# CPM-_Circuital_Printing_Machine_2020-06-.net
KiCad netlist of a schematic drawn in EasyEDA
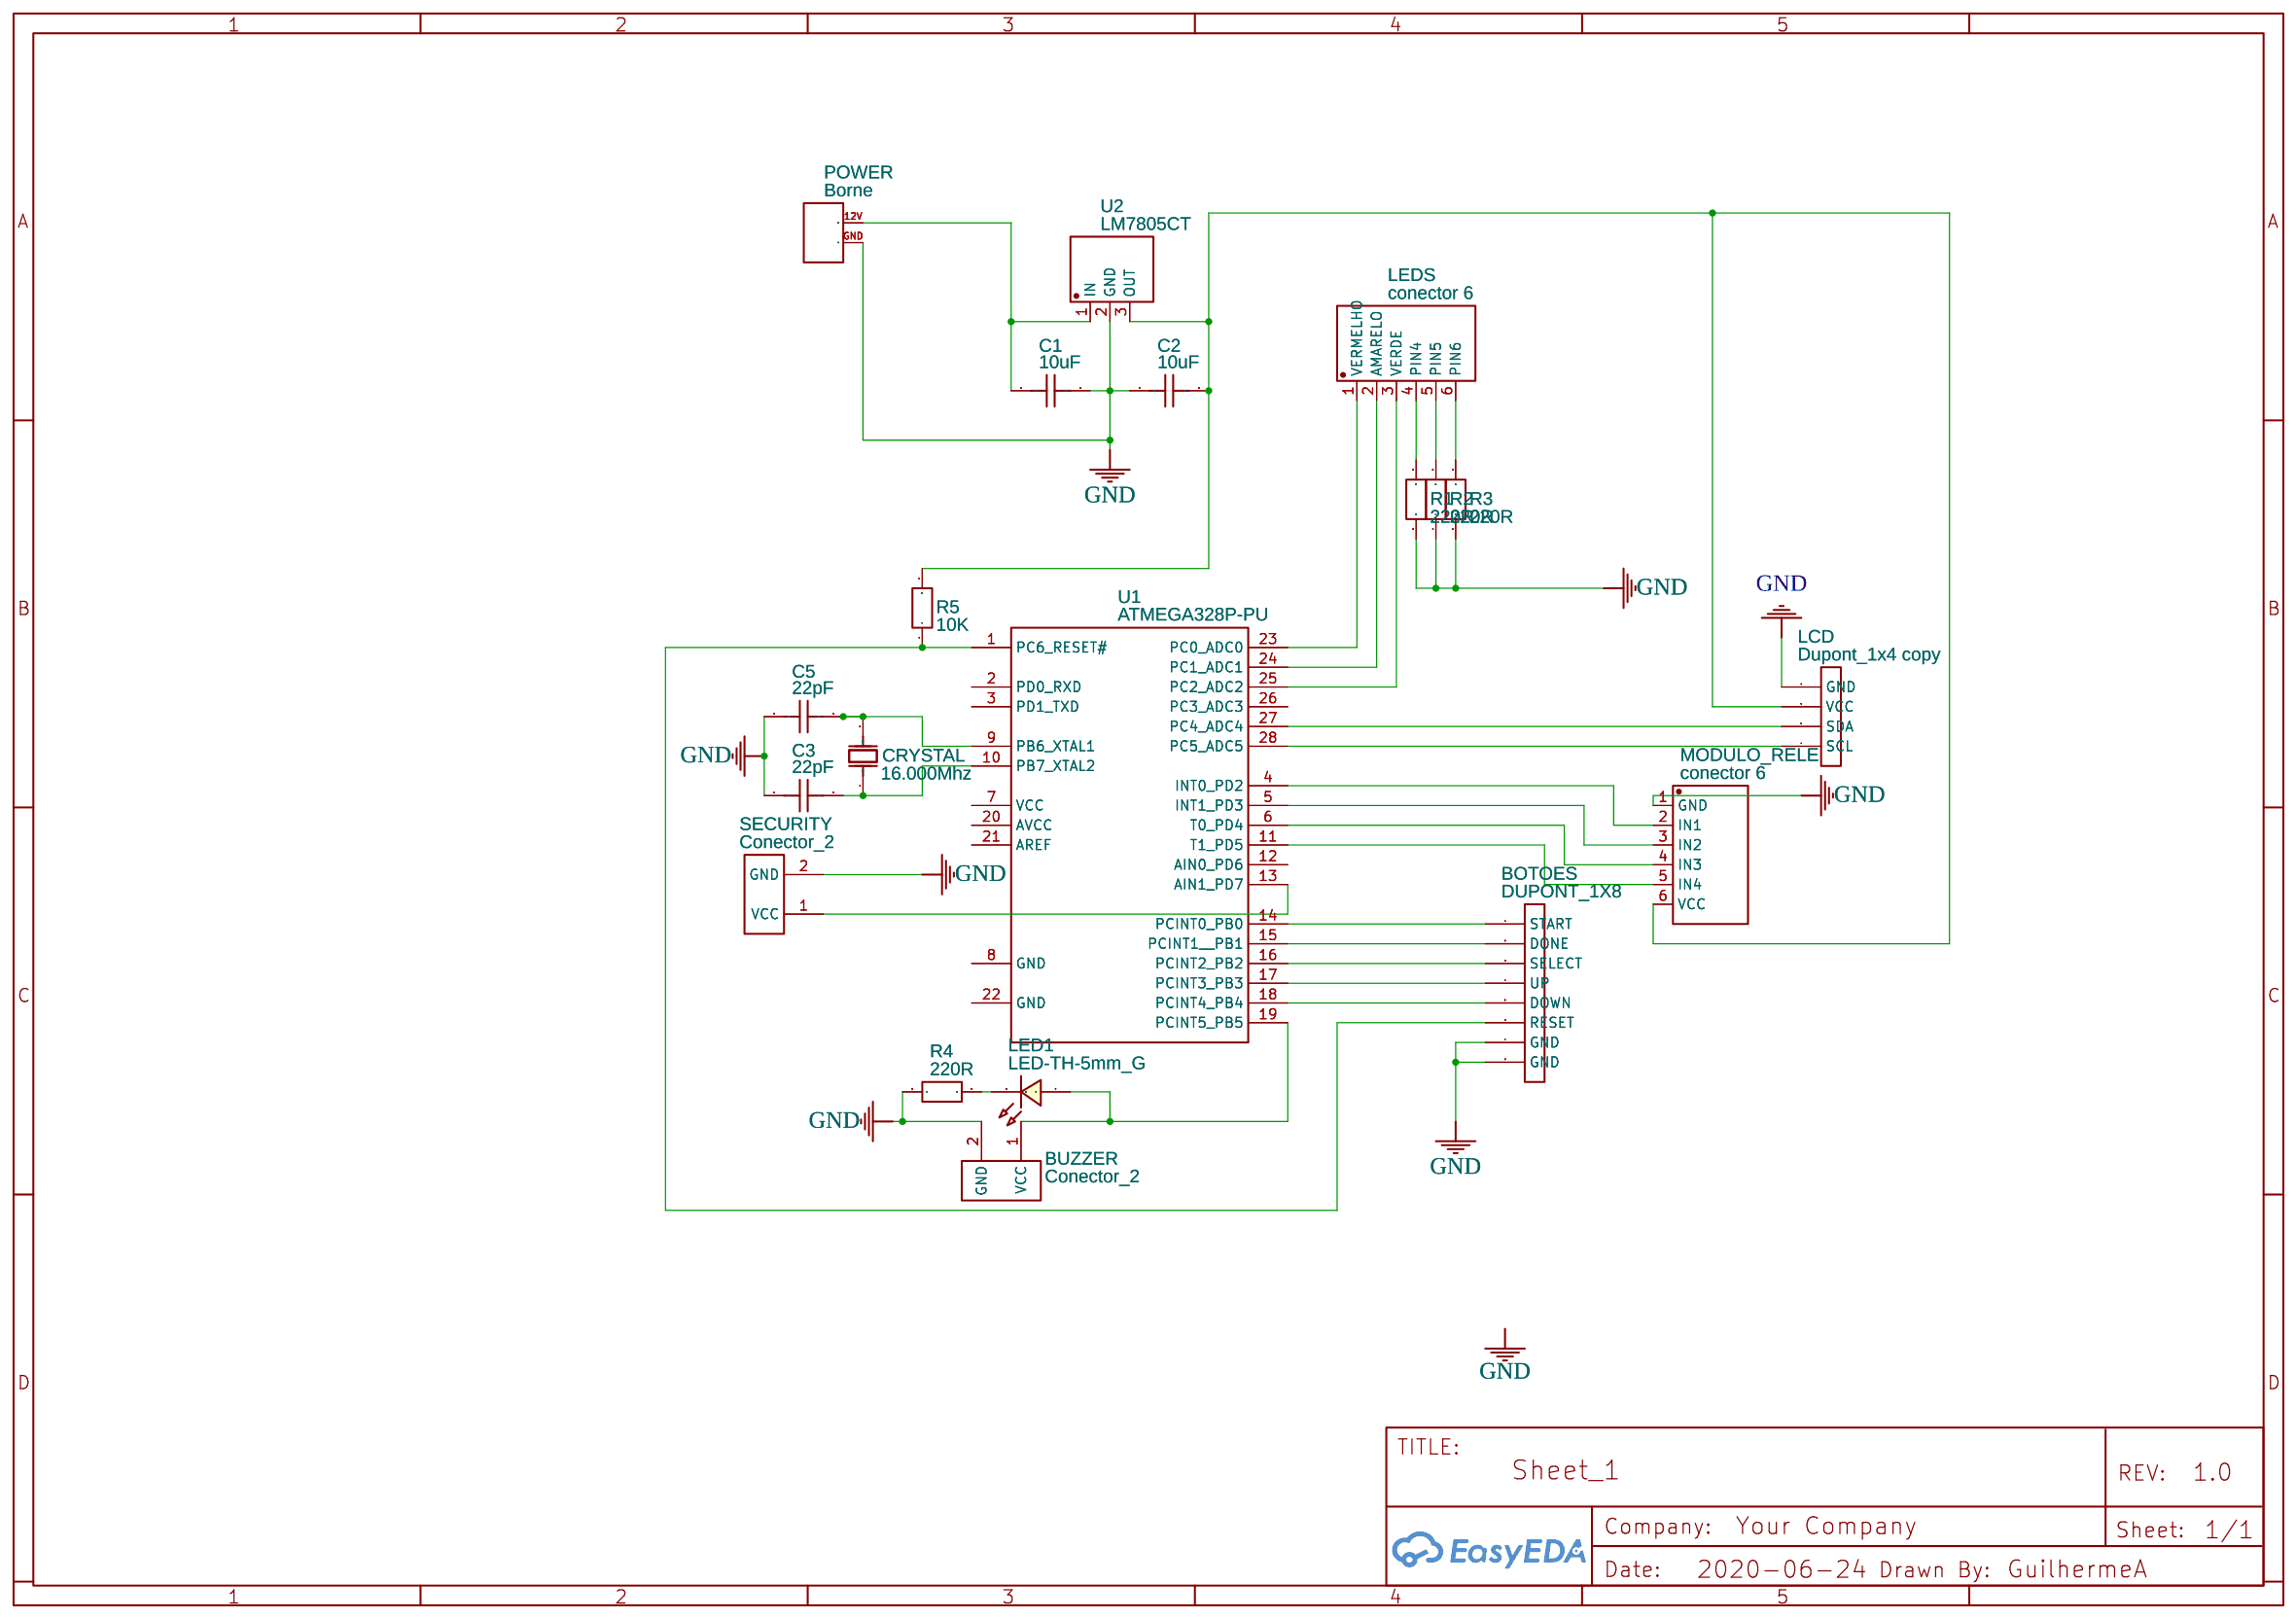
[diagram p0: schematic sheet]

(export (version "E")
  (design (tool "Eeschema 10.0.6"))
  (components
    (comp (ref "BOTOES")
      (value "DUPONT_1X8")
      (fields (field (name "BOM_Manufacturer Part") "Conector_dupont"))
      (libsource (lib "") (part "DUPONT_1X8"))
    )
    (comp (ref "BUZZER")
      (value "Conector_2")
      (fields (field (name "BOM_Manufacturer Part") "Conector2"))
      (libsource (lib "") (part "Conector_2"))
    )
    (comp (ref "C1") (value "10uF") (libsource (lib "") (part "C_RAD-0.1_US")))
    (comp (ref "C2") (value "10uF") (libsource (lib "") (part "C_RAD-0.1_US")))
    (comp (ref "C3") (value "22pF") (libsource (lib "") (part "C_RAD-0.1_US")))
    (comp (ref "C5") (value "22pF") (libsource (lib "") (part "C_RAD-0.1_US")))
    (comp (ref "CRYSTAL")
      (value "16.000Mhz")
      (fields
        (field (name "BOM_Manufacturer Part") "5S0-2700A2020-00")
        (field (name "BOM_Supplier Part") "C389767")
      )
      (libsource (lib "") (part "5S0-2700A2020-00"))
    )
    (comp (ref "LCD")
      (value "Dupont_1x4 copy")
      (fields (field (name "BOM_Manufacturer Part") "Conector_dupont"))
      (libsource (lib "") (part "Dupont_1x4 copy"))
    )
    (comp (ref "LED1")
      (value "LED-TH-5mm_G")
      (fields
        (field (name "BOM_Manufacturer Part") "333-2SYGD/S530-E2")
        (field (name "BOM_Supplier Part") "C88163")
      )
      (libsource (lib "") (part "LED-TH-5mm_G"))
    )
    (comp (ref "LEDS")
      (value "conector 6")
      (fields
        (field (name "BOM_Manufacturer Part") "425Connectors- -07P-2.5mmWhite Grey")
        (field (name "BOM_Supplier Part") "C89538")
      )
      (libsource (lib "") (part "conector 6"))
    )
    (comp (ref "MODULO_RELE")
      (value "conector 6")
      (fields
        (field (name "BOM_Manufacturer Part") "425Connectors- -07P-2.5mmWhite Grey")
        (field (name "BOM_Supplier Part") "C89538")
      )
      (libsource (lib "") (part "conector 6_1"))
    )
    (comp (ref "POWER") (value "Borne") (libsource (lib "") (part "Borne")))
    (comp (ref "R1") (value "220R") (libsource (lib "") (part "R_AXIAL-0.3_EU")))
    (comp (ref "R2") (value "220R") (libsource (lib "") (part "R_AXIAL-0.3_EU")))
    (comp (ref "R3") (value "220R") (libsource (lib "") (part "R_AXIAL-0.3_EU")))
    (comp (ref "R4") (value "220R") (libsource (lib "") (part "R_AXIAL-0.3_EU_1")))
    (comp (ref "R5") (value "10K") (libsource (lib "") (part "R_AXIAL-0.3_EU")))
    (comp (ref "SECURITY")
      (value "Conector_2")
      (fields (field (name "BOM_Manufacturer Part") "Conector2"))
      (libsource (lib "") (part "Conector_2_1"))
    )
    (comp (ref "U1")
      (value "ATMEGA328P-PU")
      (fields (field (name "BOM_Supplier Part") "C33901"))
      (libsource (lib "") (part "ATMEGA328P-PU"))
    )
    (comp (ref "U2")
      (value "LM7805CT")
      (fields (field (name "BOM_Supplier Part") "C22146"))
      (libsource (lib "") (part "LM7805CT"))
    )
  )
  (nets
    (net (code "1") (name "GND") (class "Default")
      (node (ref "BOTOES") (pin "7") (pinfunction "GND_7") (pintype "unspecified"))
      (node (ref "BOTOES") (pin "8") (pinfunction "GND_8") (pintype "unspecified"))
      (node (ref "BUZZER") (pin "2") (pinfunction "GND_2") (pintype "unspecified"))
      (node (ref "C1") (pin "2") (pinfunction "2_2") (pintype "unspecified"))
      (node (ref "C2") (pin "1") (pinfunction "1_1") (pintype "unspecified"))
      (node (ref "C3") (pin "1") (pinfunction "1_1") (pintype "unspecified"))
      (node (ref "C5") (pin "1") (pinfunction "1_1") (pintype "unspecified"))
      (node (ref "LCD") (pin "1") (pinfunction "GND_1") (pintype "unspecified"))
      (node (ref "MODULO_RELE") (pin "1") (pinfunction "GND_1") (pintype "unspecified"))
      (node (ref "POWER") (pin "GND") (pinfunction "1_GND") (pintype "unspecified"))
      (node (ref "R1") (pin "1") (pinfunction "1_1") (pintype "unspecified"))
      (node (ref "R2") (pin "1") (pinfunction "1_1") (pintype "unspecified"))
      (node (ref "R3") (pin "1") (pinfunction "1_1") (pintype "unspecified"))
      (node (ref "R4") (pin "2") (pinfunction "2_2") (pintype "unspecified"))
      (node (ref "SECURITY") (pin "2") (pinfunction "GND_2") (pintype "unspecified"))
      (node (ref "U2") (pin "2") (pinfunction "GND_2") (pintype "unspecified"))
    )
    (net (code "2") (name "Net-(BOTOES-DONE)") (class "Default")
      (node (ref "BOTOES") (pin "2") (pinfunction "DONE_2") (pintype "unspecified"))
      (node (ref "U1") (pin "15") (pinfunction "PCINT1__PB1_15") (pintype "bidirectional"))
    )
    (net (code "3") (name "Net-(BOTOES-DOWN)") (class "Default")
      (node (ref "BOTOES") (pin "5") (pinfunction "DOWN_5") (pintype "unspecified"))
      (node (ref "U1") (pin "18") (pinfunction "PCINT4_PB4_18") (pintype "bidirectional"))
    )
    (net (code "4") (name "Net-(BOTOES-RESET)") (class "Default")
      (node (ref "BOTOES") (pin "6") (pinfunction "RESET_6") (pintype "unspecified"))
      (node (ref "R5") (pin "1") (pinfunction "1_1") (pintype "unspecified"))
      (node (ref "U1") (pin "1") (pinfunction "PC6_RESET#_1") (pintype "bidirectional"))
    )
    (net (code "5") (name "Net-(BOTOES-SELECT)") (class "Default")
      (node (ref "BOTOES") (pin "3") (pinfunction "SELECT_3") (pintype "unspecified"))
      (node (ref "U1") (pin "16") (pinfunction "PCINT2_PB2_16") (pintype "bidirectional"))
    )
    (net (code "6") (name "Net-(BOTOES-START)") (class "Default")
      (node (ref "BOTOES") (pin "1") (pinfunction "START_1") (pintype "unspecified"))
      (node (ref "U1") (pin "14") (pinfunction "PCINT0_PB0_14") (pintype "bidirectional"))
    )
    (net (code "7") (name "Net-(BOTOES-UP)") (class "Default")
      (node (ref "BOTOES") (pin "4") (pinfunction "UP_4") (pintype "unspecified"))
      (node (ref "U1") (pin "17") (pinfunction "PCINT3_PB3_17") (pintype "bidirectional"))
    )
    (net (code "8") (name "Net-(BUZZER-VCC)") (class "Default")
      (node (ref "BUZZER") (pin "1") (pinfunction "VCC_1") (pintype "unspecified"))
      (node (ref "LED1") (pin "1") (pinfunction "1_1") (pintype "unspecified"))
      (node (ref "U1") (pin "19") (pinfunction "PCINT5_PB5_19") (pintype "bidirectional"))
    )
    (net (code "9") (name "Net-(CRYSTAL-OSC1)") (class "Default")
      (node (ref "C3") (pin "2") (pinfunction "2_2") (pintype "unspecified"))
      (node (ref "CRYSTAL") (pin "1") (pinfunction "OSC1_1") (pintype "input"))
      (node (ref "U1") (pin "10") (pinfunction "PB7_XTAL2_10") (pintype "bidirectional"))
    )
    (net (code "10") (name "Net-(CRYSTAL-OSC2)") (class "Default")
      (node (ref "C5") (pin "2") (pinfunction "2_2") (pintype "unspecified"))
      (node (ref "CRYSTAL") (pin "2") (pinfunction "OSC2_2") (pintype "input"))
      (node (ref "U1") (pin "9") (pinfunction "PB6_XTAL1_9") (pintype "bidirectional"))
    )
    (net (code "11") (name "Net-(LCD-SCL)") (class "Default")
      (node (ref "LCD") (pin "4") (pinfunction "SCL_4") (pintype "unspecified"))
      (node (ref "U1") (pin "28") (pinfunction "PC5_ADC5_28") (pintype "bidirectional"))
    )
    (net (code "12") (name "Net-(LCD-SDA)") (class "Default")
      (node (ref "LCD") (pin "3") (pinfunction "SDA_3") (pintype "unspecified"))
      (node (ref "U1") (pin "27") (pinfunction "PC4_ADC4_27") (pintype "bidirectional"))
    )
    (net (code "13") (name "Net-(LCD-VCC)") (class "Default")
      (node (ref "C2") (pin "2") (pinfunction "2_2") (pintype "unspecified"))
      (node (ref "LCD") (pin "2") (pinfunction "VCC_2") (pintype "unspecified"))
      (node (ref "MODULO_RELE") (pin "6") (pinfunction "VCC_6") (pintype "unspecified"))
      (node (ref "R5") (pin "2") (pinfunction "2_2") (pintype "unspecified"))
      (node (ref "U2") (pin "3") (pinfunction "OUT_3") (pintype "unspecified"))
    )
    (net (code "14") (name "Net-(LED1-Pad2)") (class "Default")
      (node (ref "LED1") (pin "2") (pinfunction "2_2") (pintype "unspecified"))
      (node (ref "R4") (pin "1") (pinfunction "1_1") (pintype "unspecified"))
    )
    (net (code "15") (name "Net-(LEDS-AMARELO)") (class "Default")
      (node (ref "LEDS") (pin "2") (pinfunction "AMARELO_2") (pintype "unspecified"))
      (node (ref "U1") (pin "24") (pinfunction "PC1_ADC1_24") (pintype "bidirectional"))
    )
    (net (code "16") (name "Net-(LEDS-PIN4)") (class "Default")
      (node (ref "LEDS") (pin "4") (pinfunction "PIN4_4") (pintype "unspecified"))
      (node (ref "R1") (pin "2") (pinfunction "2_2") (pintype "unspecified"))
    )
    (net (code "17") (name "Net-(LEDS-PIN5)") (class "Default")
      (node (ref "LEDS") (pin "5") (pinfunction "PIN5_5") (pintype "unspecified"))
      (node (ref "R2") (pin "2") (pinfunction "2_2") (pintype "unspecified"))
    )
    (net (code "18") (name "Net-(LEDS-PIN6)") (class "Default")
      (node (ref "LEDS") (pin "6") (pinfunction "PIN6_6") (pintype "unspecified"))
      (node (ref "R3") (pin "2") (pinfunction "2_2") (pintype "unspecified"))
    )
    (net (code "19") (name "Net-(LEDS-VERDE)") (class "Default")
      (node (ref "LEDS") (pin "3") (pinfunction "VERDE_3") (pintype "unspecified"))
      (node (ref "U1") (pin "25") (pinfunction "PC2_ADC2_25") (pintype "bidirectional"))
    )
    (net (code "20") (name "Net-(LEDS-VERMELHO)") (class "Default")
      (node (ref "LEDS") (pin "1") (pinfunction "VERMELHO_1") (pintype "unspecified"))
      (node (ref "U1") (pin "23") (pinfunction "PC0_ADC0_23") (pintype "bidirectional"))
    )
    (net (code "21") (name "Net-(MODULO_RELE-IN1)") (class "Default")
      (node (ref "MODULO_RELE") (pin "2") (pinfunction "IN1_2") (pintype "unspecified"))
      (node (ref "U1") (pin "4") (pinfunction "INT0_PD2_4") (pintype "bidirectional"))
    )
    (net (code "22") (name "Net-(MODULO_RELE-IN2)") (class "Default")
      (node (ref "MODULO_RELE") (pin "3") (pinfunction "IN2_3") (pintype "unspecified"))
      (node (ref "U1") (pin "5") (pinfunction "INT1_PD3_5") (pintype "bidirectional"))
    )
    (net (code "23") (name "Net-(MODULO_RELE-IN3)") (class "Default")
      (node (ref "MODULO_RELE") (pin "4") (pinfunction "IN3_4") (pintype "unspecified"))
      (node (ref "U1") (pin "6") (pinfunction "T0_PD4_6") (pintype "bidirectional"))
    )
    (net (code "24") (name "Net-(MODULO_RELE-IN4)") (class "Default")
      (node (ref "MODULO_RELE") (pin "5") (pinfunction "IN4_5") (pintype "unspecified"))
      (node (ref "U1") (pin "11") (pinfunction "T1_PD5_11") (pintype "bidirectional"))
    )
    (net (code "25") (name "Net-(POWER-2)") (class "Default")
      (node (ref "C1") (pin "1") (pinfunction "1_1") (pintype "unspecified"))
      (node (ref "POWER") (pin "12V") (pinfunction "2_12V") (pintype "unspecified"))
      (node (ref "U2") (pin "1") (pinfunction "IN_1") (pintype "unspecified"))
    )
    (net (code "26") (name "Net-(SECURITY-VCC)") (class "Default")
      (node (ref "SECURITY") (pin "1") (pinfunction "VCC_1") (pintype "unspecified"))
      (node (ref "U1") (pin "13") (pinfunction "AIN1_PD7_13") (pintype "bidirectional"))
    )
    (net (code "27") (name "unconnected-(U1-AIN0_PD6-Pad12)") (class "Default")
      (node (ref "U1") (pin "12") (pinfunction "AIN0_PD6_12") (pintype "bidirectional"))
    )
    (net (code "28") (name "unconnected-(U1-AREF-Pad21)") (class "Default")
      (node (ref "U1") (pin "21") (pinfunction "AREF_21") (pintype "passive"))
    )
    (net (code "29") (name "unconnected-(U1-AVCC-Pad20)") (class "Default")
      (node (ref "U1") (pin "20") (pinfunction "AVCC_20") (pintype "passive"))
    )
    (net (code "30") (name "unconnected-(U1-GND-Pad8)") (class "Default")
      (node (ref "U1") (pin "8") (pinfunction "GND_8") (pintype "passive"))
    )
    (net (code "31") (name "unconnected-(U1-GND-Pad22)") (class "Default")
      (node (ref "U1") (pin "22") (pinfunction "GND_22") (pintype "passive"))
    )
    (net (code "32") (name "unconnected-(U1-PC3_ADC3-Pad26)") (class "Default")
      (node (ref "U1") (pin "26") (pinfunction "PC3_ADC3_26") (pintype "bidirectional"))
    )
    (net (code "33") (name "unconnected-(U1-PD0_RXD-Pad2)") (class "Default")
      (node (ref "U1") (pin "2") (pinfunction "PD0_RXD_2") (pintype "bidirectional"))
    )
    (net (code "34") (name "unconnected-(U1-PD1_TXD-Pad3)") (class "Default")
      (node (ref "U1") (pin "3") (pinfunction "PD1_TXD_3") (pintype "bidirectional"))
    )
    (net (code "35") (name "unconnected-(U1-VCC-Pad7)") (class "Default")
      (node (ref "U1") (pin "7") (pinfunction "VCC_7") (pintype "passive"))
    )
  )
)
